# RCShield-v3.net
KiCad netlist of a schematic drawn in EAGLE
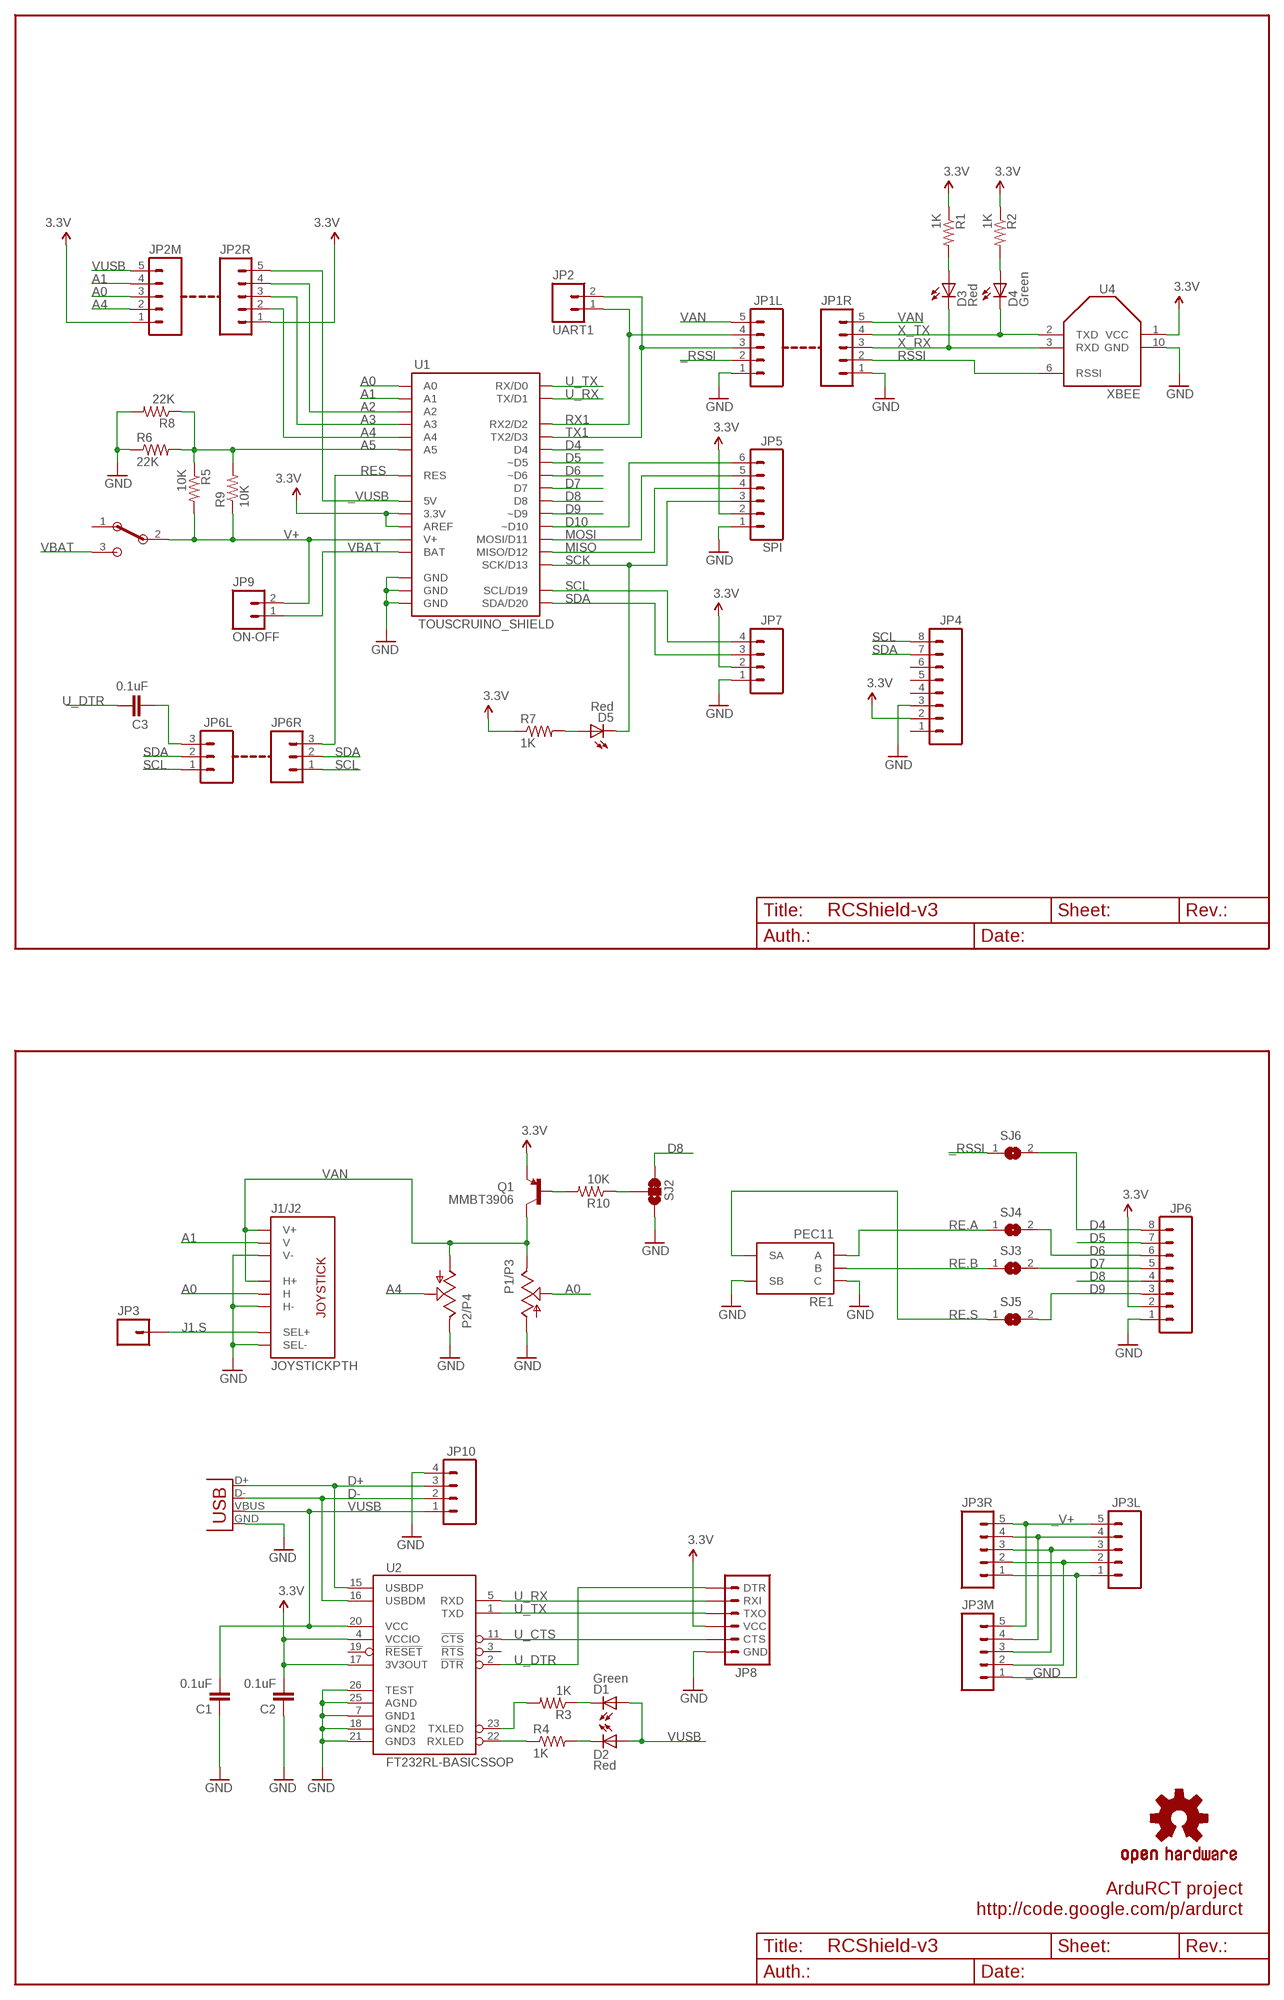
[diagram p0: schematic, sheet 1]

(export (version "E")
  (design (tool "Eeschema 10.0.6"))
  (components
    (comp (ref "C1")
      (value "0.1uF")
      (footprint "eagle-import:0805")
      (libsource (lib "eagle-import") (part "CAP0805"))
    )
    (comp (ref "C2")
      (value "0.1uF")
      (footprint "eagle-import:0805")
      (libsource (lib "eagle-import") (part "CAP0805"))
    )
    (comp (ref "C3")
      (value "0.1uF")
      (footprint "eagle-import:0805")
      (libsource (lib "eagle-import") (part "CAP0805"))
    )
    (comp (ref "D1")
      (value "Green")
      (footprint "eagle-import:LED")
      (libsource (lib "eagle-import") (part "LED"))
    )
    (comp (ref "D2")
      (value "Red")
      (footprint "eagle-import:LED")
      (libsource (lib "eagle-import") (part "LED"))
    )
    (comp (ref "D3")
      (value "Red")
      (footprint "eagle-import:LED")
      (libsource (lib "eagle-import") (part "LED"))
    )
    (comp (ref "D4")
      (value "Green")
      (footprint "eagle-import:LED")
      (libsource (lib "eagle-import") (part "LED"))
    )
    (comp (ref "D5")
      (value "Red")
      (footprint "eagle-import:LED")
      (libsource (lib "eagle-import") (part "LED"))
    )
    (comp (ref "J1/J2")
      (value "JOYSTICKPTH")
      (footprint "eagle-import:JOYSTICK")
      (libsource (lib "eagle-import") (part "JOYSTICKPTH"))
    )
    (comp (ref "JP1L")
      (value "M05")
      (footprint "eagle-import:2+3")
      (libsource (lib "eagle-import") (part "M05"))
    )
    (comp (ref "JP1R")
      (value "M05")
      (footprint "eagle-import:2+3")
      (libsource (lib "eagle-import") (part "M05"))
    )
    (comp (ref "JP2")
      (value "UART1")
      (footprint "eagle-import:1X02")
      (libsource (lib "eagle-import") (part "M02"))
    )
    (comp (ref "JP2M")
      (value "M05")
      (footprint "eagle-import:2+3")
      (libsource (lib "eagle-import") (part "M05"))
    )
    (comp (ref "JP2R")
      (value "M05")
      (footprint "eagle-import:2+3")
      (libsource (lib "eagle-import") (part "M05"))
    )
    (comp (ref "JP3")
      (value "M01PTH")
      (footprint "eagle-import:1X01")
      (libsource (lib "eagle-import") (part "M01PTH"))
    )
    (comp (ref "JP3L")
      (value "M05")
      (footprint "eagle-import:2+3")
      (libsource (lib "eagle-import") (part "M05"))
    )
    (comp (ref "JP3M")
      (value "M05")
      (footprint "eagle-import:2+3")
      (libsource (lib "eagle-import") (part "M05"))
    )
    (comp (ref "JP3R")
      (value "M05")
      (footprint "eagle-import:2+3")
      (libsource (lib "eagle-import") (part "M05"))
    )
    (comp (ref "JP4")
      (value "M08")
      (footprint "eagle-import:1X08")
      (libsource (lib "eagle-import") (part "M08"))
    )
    (comp (ref "JP5")
      (value "SPI")
      (footprint "eagle-import:1X06")
      (libsource (lib "eagle-import") (part "M06SIP"))
    )
    (comp (ref "JP6")
      (value "M08")
      (footprint "eagle-import:1X08")
      (libsource (lib "eagle-import") (part "M08"))
    )
    (comp (ref "JP6L")
      (value "M03PTH")
      (footprint "eagle-import:1X03")
      (libsource (lib "eagle-import") (part "M03PTH"))
    )
    (comp (ref "JP6R")
      (value "M03PTH")
      (footprint "eagle-import:1X03")
      (libsource (lib "eagle-import") (part "M03PTH"))
    )
    (comp (ref "JP7")
      (value "M04")
      (footprint "eagle-import:1X04")
      (libsource (lib "eagle-import") (part "M04"))
    )
    (comp (ref "JP8")
      (value "ARDUINO_SERIAL_PROGRAM")
      (footprint "eagle-import:1X06_F")
      (libsource (lib "eagle-import") (part "ARDUINO_SERIAL_PROGRAM"))
    )
    (comp (ref "JP9")
      (value "ON-OFF")
      (footprint "eagle-import:1X02")
      (libsource (lib "eagle-import") (part "M02"))
    )
    (comp (ref "JP10")
      (value "M04")
      (footprint "eagle-import:1X04")
      (libsource (lib "eagle-import") (part "M04"))
    )
    (comp (ref "P1/P3")
      (value "POT")
      (footprint "eagle-import:ALPS_POT")
      (libsource (lib "eagle-import") (part "POT"))
    )
    (comp (ref "P2/P4")
      (value "POT")
      (footprint "eagle-import:ALPS_POT")
      (libsource (lib "eagle-import") (part "POT"))
    )
    (comp (ref "Q1")
      (value "MMBT3906")
      (footprint "eagle-import:SOT23-3")
      (libsource (lib "eagle-import") (part "TRANSISTOR_PNPSMD"))
    )
    (comp (ref "R1")
      (value "1K")
      (footprint "eagle-import:0805")
      (libsource (lib "eagle-import") (part "RESISTOR0805-RES"))
    )
    (comp (ref "R2")
      (value "1K")
      (footprint "eagle-import:0805")
      (libsource (lib "eagle-import") (part "RESISTOR0805-RES"))
    )
    (comp (ref "R3")
      (value "1K")
      (footprint "eagle-import:0805")
      (libsource (lib "eagle-import") (part "RESISTOR0805-RES"))
    )
    (comp (ref "R4")
      (value "1K")
      (footprint "eagle-import:0805")
      (libsource (lib "eagle-import") (part "RESISTOR0805-RES"))
    )
    (comp (ref "R5")
      (value "10K")
      (footprint "eagle-import:0805")
      (libsource (lib "eagle-import") (part "RESISTOR0805-RES"))
    )
    (comp (ref "R6")
      (value "22K")
      (footprint "eagle-import:0805")
      (libsource (lib "eagle-import") (part "RESISTOR0805-RES"))
    )
    (comp (ref "R7")
      (value "1K")
      (footprint "eagle-import:0805")
      (libsource (lib "eagle-import") (part "RESISTOR0805-RES"))
    )
    (comp (ref "R8")
      (value "22K")
      (footprint "eagle-import:0207_7")
      (libsource (lib "eagle-import") (part "R-US_0207/7"))
    )
    (comp (ref "R9")
      (value "10K")
      (footprint "eagle-import:0207_7")
      (libsource (lib "eagle-import") (part "R-US_0207/7"))
    )
    (comp (ref "R10")
      (value "10K")
      (footprint "eagle-import:0805")
      (libsource (lib "eagle-import") (part "RESISTOR0805-RES"))
    )
    (comp (ref "RE1")
      (value "PEC11")
      (footprint "eagle-import:PEC11")
      (libsource (lib "eagle-import") (part "PEC11"))
    )
    (comp (ref "S4")
      (value "EG1224")
      (footprint "eagle-import:EG1224")
      (libsource (lib "eagle-import") (part "EG1224"))
    )
    (comp (ref "SJ2")
      (value "SJ_2WAYS_1-2W")
      (footprint "eagle-import:SJ_2WAYS_1-2")
      (libsource (lib "eagle-import") (part "SJ_2WAYS_1-2W"))
    )
    (comp (ref "SJ3") (value "SJ") (footprint "eagle-import:SJ") (libsource (lib "eagle-import") (part "SJ")))
    (comp (ref "SJ4") (value "SJ") (footprint "eagle-import:SJ") (libsource (lib "eagle-import") (part "SJ")))
    (comp (ref "SJ5") (value "SJ") (footprint "eagle-import:SJ") (libsource (lib "eagle-import") (part "SJ")))
    (comp (ref "SJ6") (value "SJ") (footprint "eagle-import:SJ") (libsource (lib "eagle-import") (part "SJ")))
    (comp (ref "U$1")
      (value "OSHW-LOGOM")
      (footprint "eagle-import:OSHW-LOGO-M")
      (libsource (lib "eagle-import") (part "OSHW-LOGOM"))
    )
    (comp (ref "U1")
      (value "TOUSCRUINO_SHIELD")
      (footprint "eagle-import:TOUSCRUINO_SHIELD_SPLIT")
      (libsource (lib "eagle-import") (part "TOUSCRUINO_SHIELDSPLIT"))
    )
    (comp (ref "U2")
      (value "FT232RL-BASICSSOP")
      (footprint "eagle-import:SSOP28DB")
      (libsource (lib "eagle-import") (part "FT232RL-BASICSSOP"))
    )
    (comp (ref "U4")
      (value "XBEE")
      (footprint "eagle-import:XBEE-SMD")
      (libsource (lib "eagle-import") (part "XBEE-RSSI"))
    )
    (comp (ref "X1")
      (value "USB-MICROB")
      (footprint "eagle-import:USB-MICROB")
      (libsource (lib "eagle-import") (part "USB-MICROB"))
    )
  )
  (nets
    (net (code "1") (name "/A0") (class "Default")
      (node (ref "J1/J2") (pin "H2") (pinfunction "H_H2") (pintype "bidirectional"))
      (node (ref "JP2M") (pin "3") (pinfunction "3_3") (pintype "passive"))
      (node (ref "P1/P3") (pin "P$2") (pinfunction "S_P$2") (pintype "passive"))
      (node (ref "U1") (pin "A0") (pinfunction "A0_A0") (pintype "bidirectional"))
    )
    (net (code "2") (name "/A1") (class "Default")
      (node (ref "J1/J2") (pin "V2") (pinfunction "V_V2") (pintype "bidirectional"))
      (node (ref "JP2M") (pin "4") (pinfunction "4_4") (pintype "passive"))
      (node (ref "U1") (pin "A1") (pinfunction "A1_A1") (pintype "bidirectional"))
    )
    (net (code "3") (name "/A2") (class "Default")
      (node (ref "JP2R") (pin "4") (pinfunction "4_4") (pintype "passive"))
      (node (ref "U1") (pin "A2") (pinfunction "A2_A2") (pintype "bidirectional"))
    )
    (net (code "4") (name "/A3") (class "Default")
      (node (ref "JP2R") (pin "3") (pinfunction "3_3") (pintype "passive"))
      (node (ref "U1") (pin "A3") (pinfunction "A3_A3") (pintype "bidirectional"))
    )
    (net (code "5") (name "/A4") (class "Default")
      (node (ref "JP2M") (pin "2") (pinfunction "2_2") (pintype "passive"))
      (node (ref "JP2R") (pin "2") (pinfunction "2_2") (pintype "passive"))
      (node (ref "P2/P4") (pin "P$2") (pinfunction "S_P$2") (pintype "passive"))
      (node (ref "U1") (pin "A4") (pinfunction "A4_A4") (pintype "bidirectional"))
    )
    (net (code "6") (name "/A5") (class "Default")
      (node (ref "R5") (pin "1") (pinfunction "1_1") (pintype "passive"))
      (node (ref "R6") (pin "2") (pinfunction "2_2") (pintype "passive"))
      (node (ref "R8") (pin "1") (pinfunction "1_1") (pintype "passive"))
      (node (ref "R9") (pin "2") (pinfunction "2_2") (pintype "passive"))
      (node (ref "U1") (pin "A5") (pinfunction "A5_A5") (pintype "bidirectional"))
    )
    (net (code "7") (name "/D+") (class "Default")
      (node (ref "JP10") (pin "3") (pinfunction "3_3") (pintype "passive"))
      (node (ref "U2") (pin "15") (pinfunction "USBDP_15") (pintype "bidirectional"))
      (node (ref "X1") (pin "D+") (pinfunction "D+_D+") (pintype "bidirectional"))
    )
    (net (code "8") (name "/D-") (class "Default")
      (node (ref "JP10") (pin "2") (pinfunction "2_2") (pintype "passive"))
      (node (ref "U2") (pin "16") (pinfunction "USBDM_16") (pintype "bidirectional"))
      (node (ref "X1") (pin "D-") (pinfunction "D-_D-") (pintype "bidirectional"))
    )
    (net (code "9") (name "/D4") (class "Default")
      (node (ref "JP6") (pin "8") (pinfunction "8_8") (pintype "passive"))
      (node (ref "SJ6") (pin "2") (pinfunction "2_2") (pintype "passive"))
      (node (ref "U1") (pin "D4") (pinfunction "D4_D4") (pintype "bidirectional"))
    )
    (net (code "10") (name "/D5") (class "Default")
      (node (ref "JP6") (pin "7") (pinfunction "7_7") (pintype "passive"))
      (node (ref "U1") (pin "D5") (pinfunction "~{D5}_D5") (pintype "bidirectional"))
    )
    (net (code "11") (name "/D6") (class "Default")
      (node (ref "JP6") (pin "6") (pinfunction "6_6") (pintype "passive"))
      (node (ref "SJ4") (pin "2") (pinfunction "2_2") (pintype "passive"))
      (node (ref "U1") (pin "D6") (pinfunction "~{D6}_D6") (pintype "bidirectional"))
    )
    (net (code "12") (name "/D7") (class "Default")
      (node (ref "JP6") (pin "5") (pinfunction "5_5") (pintype "passive"))
      (node (ref "SJ3") (pin "2") (pinfunction "2_2") (pintype "passive"))
      (node (ref "U1") (pin "D7") (pinfunction "D7_D7") (pintype "bidirectional"))
    )
    (net (code "13") (name "/D8") (class "Default")
      (node (ref "JP6") (pin "4") (pinfunction "4_4") (pintype "passive"))
      (node (ref "SJ2") (pin "1") (pinfunction "1_1") (pintype "passive"))
      (node (ref "U1") (pin "D8") (pinfunction "D8_D8") (pintype "bidirectional"))
    )
    (net (code "14") (name "/D9") (class "Default")
      (node (ref "JP6") (pin "3") (pinfunction "3_3") (pintype "passive"))
      (node (ref "SJ5") (pin "2") (pinfunction "2_2") (pintype "passive"))
      (node (ref "U1") (pin "D9") (pinfunction "~{D9}_D9") (pintype "bidirectional"))
    )
    (net (code "15") (name "/D10") (class "Default")
      (node (ref "JP5") (pin "6") (pinfunction "6_6") (pintype "passive"))
      (node (ref "U1") (pin "D10") (pinfunction "~{D10}_D10") (pintype "bidirectional"))
    )
    (net (code "16") (name "/J1.S") (class "Default")
      (node (ref "J1/J2") (pin "B1A") (pinfunction "SEL+_B1A") (pintype "bidirectional"))
      (node (ref "JP3") (pin "1") (pinfunction "1_1") (pintype "passive"))
    )
    (net (code "17") (name "/MISO") (class "Default")
      (node (ref "JP5") (pin "4") (pinfunction "4_4") (pintype "passive"))
      (node (ref "U1") (pin "D12") (pinfunction "MISO/D12_D12") (pintype "bidirectional"))
    )
    (net (code "18") (name "/MOSI") (class "Default")
      (node (ref "JP5") (pin "5") (pinfunction "5_5") (pintype "passive"))
      (node (ref "U1") (pin "D11") (pinfunction "MOSI/D11_D11") (pintype "bidirectional"))
    )
    (net (code "19") (name "/RE.A") (class "Default")
      (node (ref "RE1") (pin "A") (pinfunction "A_A") (pintype "bidirectional"))
      (node (ref "SJ4") (pin "1") (pinfunction "1_1") (pintype "passive"))
    )
    (net (code "20") (name "/RE.B") (class "Default")
      (node (ref "RE1") (pin "B") (pinfunction "B_B") (pintype "bidirectional"))
      (node (ref "SJ3") (pin "1") (pinfunction "1_1") (pintype "passive"))
    )
    (net (code "21") (name "/RE.S") (class "Default")
      (node (ref "RE1") (pin "S1") (pinfunction "SA_S1") (pintype "bidirectional"))
      (node (ref "SJ5") (pin "1") (pinfunction "1_1") (pintype "passive"))
    )
    (net (code "22") (name "/RES") (class "Default")
      (node (ref "JP6R") (pin "3") (pinfunction "3_3") (pintype "passive"))
      (node (ref "U1") (pin "RES") (pinfunction "RES_RES") (pintype "bidirectional"))
    )
    (net (code "23") (name "/RSSI") (class "Default")
      (node (ref "JP1R") (pin "2") (pinfunction "2_2") (pintype "passive"))
      (node (ref "U4") (pin "6") (pinfunction "RSSI_6") (pintype "bidirectional"))
    )
    (net (code "24") (name "/RX1") (class "Default")
      (node (ref "JP1L") (pin "4") (pinfunction "4_4") (pintype "passive"))
      (node (ref "JP2") (pin "1") (pinfunction "1_1") (pintype "passive"))
      (node (ref "U1") (pin "D2") (pinfunction "RX2/D2_D2") (pintype "bidirectional"))
    )
    (net (code "25") (name "/SCK") (class "Default")
      (node (ref "D5") (pin "C1") (pinfunction "C_C1") (pintype "passive"))
      (node (ref "JP5") (pin "3") (pinfunction "3_3") (pintype "passive"))
      (node (ref "U1") (pin "D13") (pinfunction "SCK/D13_D13") (pintype "bidirectional"))
    )
    (net (code "26") (name "/SCL") (class "Default")
      (node (ref "JP4") (pin "8") (pinfunction "8_8") (pintype "passive"))
      (node (ref "JP6L") (pin "1") (pinfunction "1_1") (pintype "passive"))
      (node (ref "JP6R") (pin "1") (pinfunction "1_1") (pintype "passive"))
      (node (ref "JP7") (pin "4") (pinfunction "4_4") (pintype "passive"))
      (node (ref "U1") (pin "SCL") (pinfunction "SCL/D19_SCL") (pintype "bidirectional"))
    )
    (net (code "27") (name "/SDA") (class "Default")
      (node (ref "JP4") (pin "7") (pinfunction "7_7") (pintype "passive"))
      (node (ref "JP6L") (pin "2") (pinfunction "2_2") (pintype "passive"))
      (node (ref "JP6R") (pin "2") (pinfunction "2_2") (pintype "passive"))
      (node (ref "JP7") (pin "3") (pinfunction "3_3") (pintype "passive"))
      (node (ref "U1") (pin "SDA") (pinfunction "SDA/D20_SDA") (pintype "bidirectional"))
    )
    (net (code "28") (name "/TX1") (class "Default")
      (node (ref "JP1L") (pin "3") (pinfunction "3_3") (pintype "passive"))
      (node (ref "JP2") (pin "2") (pinfunction "2_2") (pintype "passive"))
      (node (ref "U1") (pin "D3") (pinfunction "TX2/D3_D3") (pintype "bidirectional"))
    )
    (net (code "29") (name "/U_CTS") (class "Default")
      (node (ref "JP8") (pin "5") (pinfunction "CTS_5") (pintype "passive"))
      (node (ref "U2") (pin "11") (pinfunction "~{CTS}_11") (pintype "bidirectional"))
    )
    (net (code "30") (name "/U_DTR") (class "Default")
      (node (ref "C3") (pin "1") (pinfunction "1_1") (pintype "passive"))
      (node (ref "JP8") (pin "1") (pinfunction "DTR_1") (pintype "passive"))
      (node (ref "U2") (pin "2") (pinfunction "~{DTR}_2") (pintype "bidirectional"))
    )
    (net (code "31") (name "/U_RX") (class "Default")
      (node (ref "JP8") (pin "2") (pinfunction "RXI_2") (pintype "passive"))
      (node (ref "U1") (pin "TX") (pinfunction "TX/D1_TX") (pintype "bidirectional"))
      (node (ref "U2") (pin "5") (pinfunction "RXD_5") (pintype "input"))
    )
    (net (code "32") (name "/U_TX") (class "Default")
      (node (ref "JP8") (pin "3") (pinfunction "TXO_3") (pintype "passive"))
      (node (ref "U1") (pin "RX") (pinfunction "RX/D0_RX") (pintype "bidirectional"))
      (node (ref "U2") (pin "1") (pinfunction "TXD_1") (pintype "output"))
    )
    (net (code "33") (name "/V+") (class "Default")
      (node (ref "JP9") (pin "2") (pinfunction "2_2") (pintype "passive"))
      (node (ref "R5") (pin "2") (pinfunction "2_2") (pintype "passive"))
      (node (ref "R9") (pin "1") (pinfunction "1_1") (pintype "passive"))
      (node (ref "S4") (pin "2") (pinfunction "2_2") (pintype "bidirectional"))
      (node (ref "U1") (pin "V+") (pinfunction "V+_V+") (pintype "bidirectional"))
    )
    (net (code "34") (name "/VAN") (class "Default")
      (node (ref "J1/J2") (pin "H1") (pinfunction "H+_H1") (pintype "bidirectional"))
      (node (ref "J1/J2") (pin "V1") (pinfunction "V+_V1") (pintype "bidirectional"))
      (node (ref "JP1L") (pin "5") (pinfunction "5_5") (pintype "passive"))
      (node (ref "JP1R") (pin "5") (pinfunction "5_5") (pintype "passive"))
      (node (ref "P1/P3") (pin "P$1") (pinfunction "E_P$1") (pintype "passive"))
      (node (ref "P2/P4") (pin "P$3") (pinfunction "A_P$3") (pintype "passive"))
      (node (ref "Q1") (pin "3") (pinfunction "C_3") (pintype "passive"))
    )
    (net (code "35") (name "/VBAT") (class "Default")
      (node (ref "JP9") (pin "1") (pinfunction "1_1") (pintype "passive"))
      (node (ref "S4") (pin "3") (pinfunction "3_3") (pintype "bidirectional"))
      (node (ref "U1") (pin "BAT") (pinfunction "BAT_BAT") (pintype "bidirectional"))
    )
    (net (code "36") (name "/VUSB") (class "Default")
      (node (ref "C1") (pin "2") (pinfunction "2_2") (pintype "passive"))
      (node (ref "D1") (pin "A1") (pinfunction "A_A1") (pintype "passive"))
      (node (ref "D2") (pin "A1") (pinfunction "A_A1") (pintype "passive"))
      (node (ref "JP10") (pin "1") (pinfunction "1_1") (pintype "passive"))
      (node (ref "JP2M") (pin "5") (pinfunction "5_5") (pintype "passive"))
      (node (ref "U2") (pin "20") (pinfunction "VCC_20") (pintype "bidirectional"))
      (node (ref "X1") (pin "VBUS") (pinfunction "VBUS_VBUS") (pintype "bidirectional"))
    )
    (net (code "37") (name "/X_RX") (class "Default")
      (node (ref "D3") (pin "C1") (pinfunction "C_C1") (pintype "passive"))
      (node (ref "JP1R") (pin "3") (pinfunction "3_3") (pintype "passive"))
      (node (ref "U4") (pin "3") (pinfunction "RXD_3") (pintype "bidirectional"))
    )
    (net (code "38") (name "/X_TX") (class "Default")
      (node (ref "D4") (pin "C1") (pinfunction "C_C1") (pintype "passive"))
      (node (ref "JP1R") (pin "4") (pinfunction "4_4") (pintype "passive"))
      (node (ref "U4") (pin "2") (pinfunction "TXD_2") (pintype "bidirectional"))
    )
    (net (code "39") (name "/_GND") (class "Default")
      (node (ref "JP3L") (pin "1") (pinfunction "1_1") (pintype "passive"))
      (node (ref "JP3M") (pin "1") (pinfunction "1_1") (pintype "passive"))
      (node (ref "JP3R") (pin "1") (pinfunction "1_1") (pintype "passive"))
    )
    (net (code "40") (name "/_RSSI") (class "Default")
      (node (ref "JP1L") (pin "2") (pinfunction "2_2") (pintype "passive"))
      (node (ref "SJ6") (pin "1") (pinfunction "1_1") (pintype "passive"))
    )
    (net (code "41") (name "/_V+") (class "Default")
      (node (ref "JP3L") (pin "5") (pinfunction "5_5") (pintype "passive"))
      (node (ref "JP3M") (pin "5") (pinfunction "5_5") (pintype "passive"))
      (node (ref "JP3R") (pin "5") (pinfunction "5_5") (pintype "passive"))
    )
    (net (code "42") (name "/_VUSB") (class "Default")
      (node (ref "JP2R") (pin "5") (pinfunction "5_5") (pintype "passive"))
      (node (ref "U1") (pin "5V") (pinfunction "5V_5V") (pintype "bidirectional"))
    )
    (net (code "43") (name "3.3V") (class "Default")
      (node (ref "C2") (pin "2") (pinfunction "2_2") (pintype "passive"))
      (node (ref "JP2M") (pin "1") (pinfunction "1_1") (pintype "passive"))
      (node (ref "JP2R") (pin "1") (pinfunction "1_1") (pintype "passive"))
      (node (ref "JP4") (pin "2") (pinfunction "2_2") (pintype "passive"))
      (node (ref "JP5") (pin "2") (pinfunction "2_2") (pintype "passive"))
      (node (ref "JP6") (pin "2") (pinfunction "2_2") (pintype "passive"))
      (node (ref "JP7") (pin "2") (pinfunction "2_2") (pintype "passive"))
      (node (ref "JP8") (pin "4") (pinfunction "VCC_4") (pintype "passive"))
      (node (ref "Q1") (pin "2") (pinfunction "E_2") (pintype "passive"))
      (node (ref "R1") (pin "1") (pinfunction "1_1") (pintype "passive"))
      (node (ref "R2") (pin "1") (pinfunction "1_1") (pintype "passive"))
      (node (ref "R7") (pin "1") (pinfunction "1_1") (pintype "passive"))
      (node (ref "U1") (pin "3.3V") (pinfunction "3.3V_3.3V") (pintype "bidirectional"))
      (node (ref "U1") (pin "AREF") (pinfunction "AREF_AREF") (pintype "bidirectional"))
      (node (ref "U2") (pin "17") (pinfunction "3V3OUT_17") (pintype "output"))
      (node (ref "U2") (pin "4") (pinfunction "VCCIO_4") (pintype "bidirectional"))
      (node (ref "U4") (pin "1") (pinfunction "VCC_1") (pintype "bidirectional"))
    )
    (net (code "44") (name "GND") (class "Default")
      (node (ref "C1") (pin "1") (pinfunction "1_1") (pintype "passive"))
      (node (ref "C2") (pin "1") (pinfunction "1_1") (pintype "passive"))
      (node (ref "J1/J2") (pin "B2A") (pinfunction "SEL-_B2A") (pintype "bidirectional"))
      (node (ref "J1/J2") (pin "H3") (pinfunction "H-_H3") (pintype "bidirectional"))
      (node (ref "J1/J2") (pin "V3") (pinfunction "V-_V3") (pintype "bidirectional"))
      (node (ref "JP10") (pin "4") (pinfunction "4_4") (pintype "passive"))
      (node (ref "JP1L") (pin "1") (pinfunction "1_1") (pintype "passive"))
      (node (ref "JP1R") (pin "1") (pinfunction "1_1") (pintype "passive"))
      (node (ref "JP4") (pin "3") (pinfunction "3_3") (pintype "passive"))
      (node (ref "JP5") (pin "1") (pinfunction "1_1") (pintype "passive"))
      (node (ref "JP6") (pin "1") (pinfunction "1_1") (pintype "passive"))
      (node (ref "JP7") (pin "1") (pinfunction "1_1") (pintype "passive"))
      (node (ref "JP8") (pin "6") (pinfunction "GND_6") (pintype "passive"))
      (node (ref "P1/P3") (pin "P$3") (pinfunction "A_P$3") (pintype "passive"))
      (node (ref "P2/P4") (pin "P$1") (pinfunction "E_P$1") (pintype "passive"))
      (node (ref "R6") (pin "1") (pinfunction "1_1") (pintype "passive"))
      (node (ref "R8") (pin "2") (pinfunction "2_2") (pintype "passive"))
      (node (ref "RE1") (pin "C") (pinfunction "C_C") (pintype "bidirectional"))
      (node (ref "RE1") (pin "S2") (pinfunction "SB_S2") (pintype "bidirectional"))
      (node (ref "SJ2") (pin "3") (pinfunction "3_3") (pintype "passive"))
      (node (ref "U1") (pin "GND@0") (pinfunction "GND_GND@0") (pintype "bidirectional"))
      (node (ref "U1") (pin "GND@1") (pinfunction "GND_GND@1") (pintype "bidirectional"))
      (node (ref "U1") (pin "GND@2") (pinfunction "GND_GND@2") (pintype "bidirectional"))
      (node (ref "U2") (pin "18") (pinfunction "GND2_18") (pintype "bidirectional"))
      (node (ref "U2") (pin "21") (pinfunction "GND3_21") (pintype "bidirectional"))
      (node (ref "U2") (pin "25") (pinfunction "AGND_25") (pintype "bidirectional"))
      (node (ref "U2") (pin "26") (pinfunction "TEST_26") (pintype "input"))
      (node (ref "U2") (pin "7") (pinfunction "GND1_7") (pintype "bidirectional"))
      (node (ref "U4") (pin "10") (pinfunction "GND_10") (pintype "bidirectional"))
      (node (ref "X1") (pin "GND") (pinfunction "GND_GND") (pintype "bidirectional"))
    )
    (net (code "45") (name "Net-(C3-Pad2)") (class "Default")
      (node (ref "C3") (pin "2") (pinfunction "2_2") (pintype "passive"))
      (node (ref "JP6L") (pin "3") (pinfunction "3_3") (pintype "passive"))
    )
    (net (code "46") (name "Net-(D1-C)") (class "Default")
      (node (ref "D1") (pin "C1") (pinfunction "C_C1") (pintype "passive"))
      (node (ref "R3") (pin "1") (pinfunction "1_1") (pintype "passive"))
    )
    (net (code "47") (name "Net-(D2-C)") (class "Default")
      (node (ref "D2") (pin "C1") (pinfunction "C_C1") (pintype "passive"))
      (node (ref "R4") (pin "2") (pinfunction "2_2") (pintype "passive"))
    )
    (net (code "48") (name "Net-(D3-A)") (class "Default")
      (node (ref "D3") (pin "A1") (pinfunction "A_A1") (pintype "passive"))
      (node (ref "R1") (pin "2") (pinfunction "2_2") (pintype "passive"))
    )
    (net (code "49") (name "Net-(D4-A)") (class "Default")
      (node (ref "D4") (pin "A1") (pinfunction "A_A1") (pintype "passive"))
      (node (ref "R2") (pin "2") (pinfunction "2_2") (pintype "passive"))
    )
    (net (code "50") (name "Net-(D5-A)") (class "Default")
      (node (ref "D5") (pin "A1") (pinfunction "A_A1") (pintype "passive"))
      (node (ref "R7") (pin "2") (pinfunction "2_2") (pintype "passive"))
    )
    (net (code "51") (name "Net-(JP3L-Pad2)") (class "Default")
      (node (ref "JP3L") (pin "2") (pinfunction "2_2") (pintype "passive"))
      (node (ref "JP3M") (pin "2") (pinfunction "2_2") (pintype "passive"))
      (node (ref "JP3R") (pin "2") (pinfunction "2_2") (pintype "passive"))
    )
    (net (code "52") (name "Net-(JP3L-Pad3)") (class "Default")
      (node (ref "JP3L") (pin "3") (pinfunction "3_3") (pintype "passive"))
      (node (ref "JP3M") (pin "3") (pinfunction "3_3") (pintype "passive"))
      (node (ref "JP3R") (pin "3") (pinfunction "3_3") (pintype "passive"))
    )
    (net (code "53") (name "Net-(JP3L-Pad4)") (class "Default")
      (node (ref "JP3L") (pin "4") (pinfunction "4_4") (pintype "passive"))
      (node (ref "JP3M") (pin "4") (pinfunction "4_4") (pintype "passive"))
      (node (ref "JP3R") (pin "4") (pinfunction "4_4") (pintype "passive"))
    )
    (net (code "54") (name "Net-(Q1-B)") (class "Default")
      (node (ref "Q1") (pin "1") (pinfunction "B_1") (pintype "passive"))
      (node (ref "R10") (pin "2") (pinfunction "2_2") (pintype "passive"))
    )
    (net (code "55") (name "Net-(R10-Pad1)") (class "Default")
      (node (ref "R10") (pin "1") (pinfunction "1_1") (pintype "passive"))
      (node (ref "SJ2") (pin "2") (pinfunction "2_2") (pintype "passive"))
    )
    (net (code "56") (name "Net-(U2-RXLED)") (class "Default")
      (node (ref "R4") (pin "1") (pinfunction "1_1") (pintype "passive"))
      (node (ref "U2") (pin "22") (pinfunction "RXLED_22") (pintype "bidirectional"))
    )
    (net (code "57") (name "Net-(U2-TXLED)") (class "Default")
      (node (ref "R3") (pin "2") (pinfunction "2_2") (pintype "passive"))
      (node (ref "U2") (pin "23") (pinfunction "TXLED_23") (pintype "bidirectional"))
    )
    (net (code "58") (name "unconnected-(JP4-Pad1)") (class "Default")
      (node (ref "JP4") (pin "1") (pinfunction "1_1") (pintype "passive"))
    )
    (net (code "59") (name "unconnected-(JP4-Pad4)") (class "Default")
      (node (ref "JP4") (pin "4") (pinfunction "4_4") (pintype "passive"))
    )
    (net (code "60") (name "unconnected-(JP4-Pad5)") (class "Default")
      (node (ref "JP4") (pin "5") (pinfunction "5_5") (pintype "passive"))
    )
    (net (code "61") (name "unconnected-(JP4-Pad6)") (class "Default")
      (node (ref "JP4") (pin "6") (pinfunction "6_6") (pintype "passive"))
    )
    (net (code "62") (name "unconnected-(S4-Pad1)") (class "Default")
      (node (ref "S4") (pin "1") (pinfunction "1_1") (pintype "bidirectional"))
    )
    (net (code "63") (name "unconnected-(U2-~{RESET}-Pad19)") (class "Default")
      (node (ref "U2") (pin "19") (pinfunction "~{RESET}_19") (pintype "bidirectional"))
    )
    (net (code "64") (name "unconnected-(U2-~{RTS}-Pad3)") (class "Default")
      (node (ref "U2") (pin "3") (pinfunction "~{RTS}_3") (pintype "bidirectional"))
    )
  )
)
